# MicrocontrollerControl.net
KiCad netlist of a schematic drawn in Altium Designer
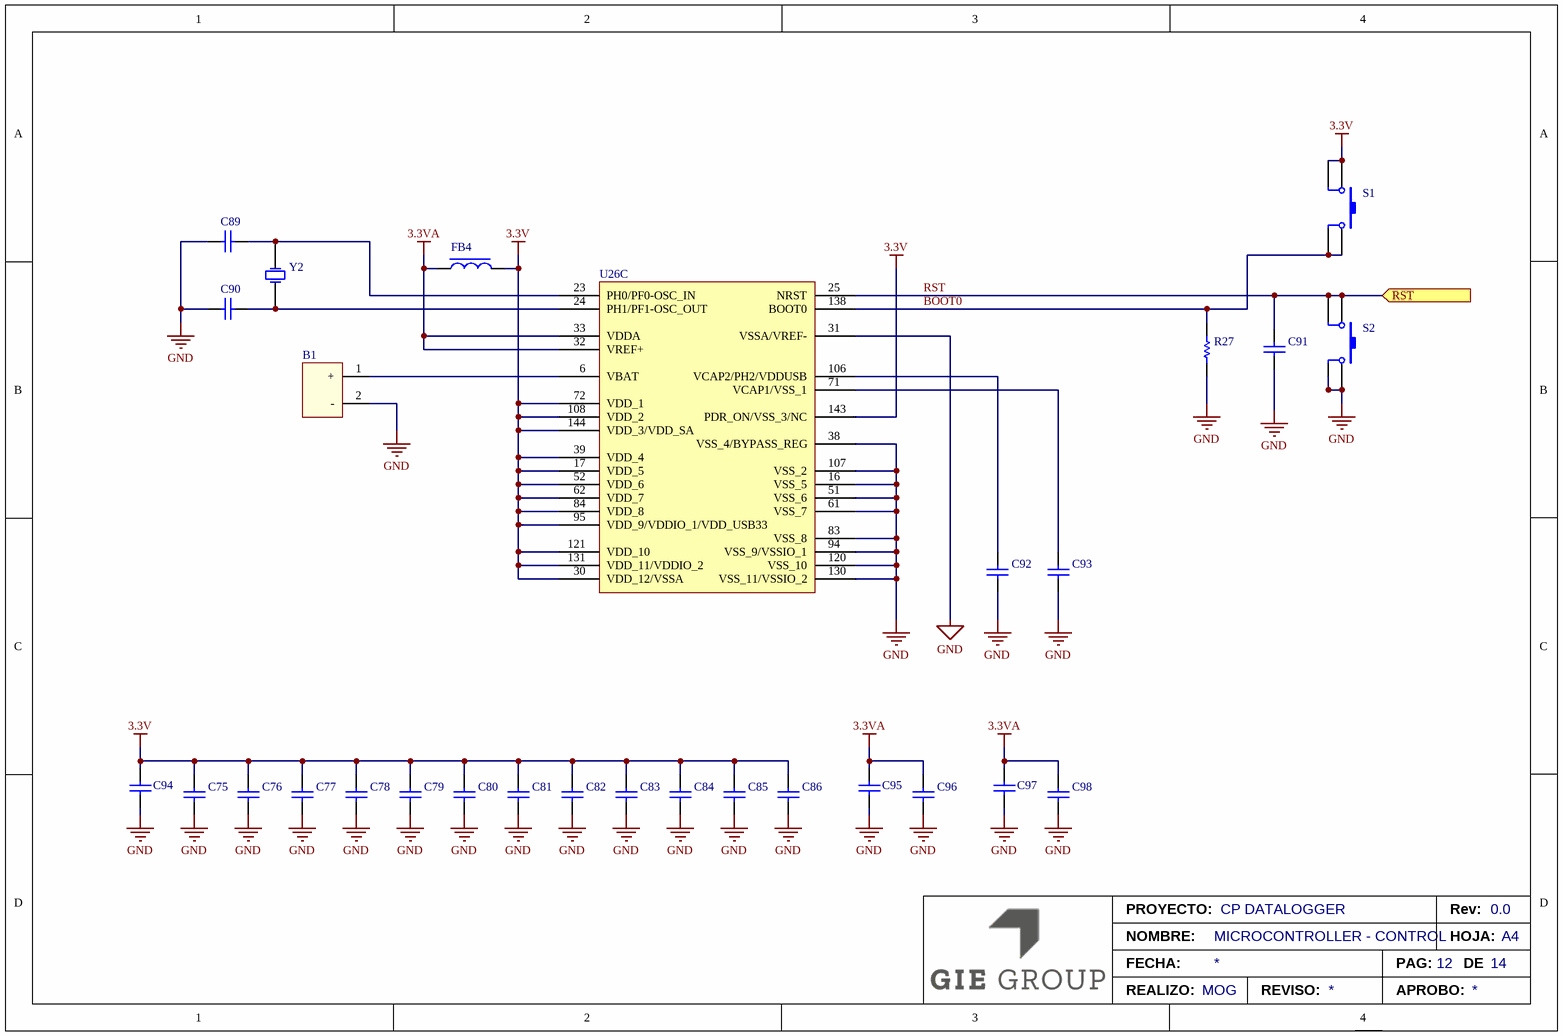
[diagram p0: MicrocontrollerControl.SchDoc]

(export (version "E")
  (design (tool "Eeschema 10.0.6"))
  (components
    (comp (ref "B1")
      (value "101")
      (footprint "Holder-CR2032-103")
      (description "HOLDER BATTERY COIN 20MM TH")
      (libsource (lib "Keystone") (part "Holder 101"))
    )
    (comp (ref "C75")
      (value "C0603C104K5RACAUTO")
      (footprint "CAP-0603")
      (description "CAP CER 0.1uF 50V X7R 0603")
      (fields (field (name "MANUFACTURER") "Kemet") (field (name "TOLERANCE") "10%"))
      (libsource (lib "Kemet") (part "C0603C104K5RACAUTO"))
    )
    (comp (ref "C76")
      (value "C0603C104K5RACAUTO")
      (footprint "CAP-0603")
      (description "CAP CER 0.1uF 50V X7R 0603")
      (fields (field (name "MANUFACTURER") "Kemet") (field (name "TOLERANCE") "10%"))
      (libsource (lib "Kemet") (part "C0603C104K5RACAUTO"))
    )
    (comp (ref "C77")
      (value "C0603C104K5RACAUTO")
      (footprint "CAP-0603")
      (description "CAP CER 0.1uF 50V X7R 0603")
      (fields (field (name "MANUFACTURER") "Kemet") (field (name "TOLERANCE") "10%"))
      (libsource (lib "Kemet") (part "C0603C104K5RACAUTO"))
    )
    (comp (ref "C78")
      (value "C0603C104K5RACAUTO")
      (footprint "CAP-0603")
      (description "CAP CER 0.1uF 50V X7R 0603")
      (fields (field (name "MANUFACTURER") "Kemet") (field (name "TOLERANCE") "10%"))
      (libsource (lib "Kemet") (part "C0603C104K5RACAUTO"))
    )
    (comp (ref "C79")
      (value "C0603C104K5RACAUTO")
      (footprint "CAP-0603")
      (description "CAP CER 0.1uF 50V X7R 0603")
      (fields (field (name "MANUFACTURER") "Kemet") (field (name "TOLERANCE") "10%"))
      (libsource (lib "Kemet") (part "C0603C104K5RACAUTO"))
    )
    (comp (ref "C80")
      (value "C0603C104K5RACAUTO")
      (footprint "CAP-0603")
      (description "CAP CER 0.1uF 50V X7R 0603")
      (fields (field (name "MANUFACTURER") "Kemet") (field (name "TOLERANCE") "10%"))
      (libsource (lib "Kemet") (part "C0603C104K5RACAUTO"))
    )
    (comp (ref "C81")
      (value "C0603C104K5RACAUTO")
      (footprint "CAP-0603")
      (description "CAP CER 0.1uF 50V X7R 0603")
      (fields (field (name "MANUFACTURER") "Kemet") (field (name "TOLERANCE") "10%"))
      (libsource (lib "Kemet") (part "C0603C104K5RACAUTO"))
    )
    (comp (ref "C82")
      (value "C0603C104K5RACAUTO")
      (footprint "CAP-0603")
      (description "CAP CER 0.1uF 50V X7R 0603")
      (fields (field (name "MANUFACTURER") "Kemet") (field (name "TOLERANCE") "10%"))
      (libsource (lib "Kemet") (part "C0603C104K5RACAUTO"))
    )
    (comp (ref "C83")
      (value "C0603C104K5RACAUTO")
      (footprint "CAP-0603")
      (description "CAP CER 0.1uF 50V X7R 0603")
      (fields (field (name "MANUFACTURER") "Kemet") (field (name "TOLERANCE") "10%"))
      (libsource (lib "Kemet") (part "C0603C104K5RACAUTO"))
    )
    (comp (ref "C84")
      (value "C0603C104K5RACAUTO")
      (footprint "CAP-0603")
      (description "CAP CER 0.1uF 50V X7R 0603")
      (fields (field (name "MANUFACTURER") "Kemet") (field (name "TOLERANCE") "10%"))
      (libsource (lib "Kemet") (part "C0603C104K5RACAUTO"))
    )
    (comp (ref "C85")
      (value "C0603C104K5RACAUTO")
      (footprint "CAP-0603")
      (description "CAP CER 0.1uF 50V X7R 0603")
      (fields (field (name "MANUFACTURER") "Kemet") (field (name "TOLERANCE") "10%"))
      (libsource (lib "Kemet") (part "C0603C104K5RACAUTO"))
    )
    (comp (ref "C86")
      (value "C0603C104K5RACAUTO")
      (footprint "CAP-0603")
      (description "CAP CER 0.1uF 50V X7R 0603")
      (fields (field (name "MANUFACTURER") "Kemet") (field (name "TOLERANCE") "10%"))
      (libsource (lib "Kemet") (part "C0603C104K5RACAUTO"))
    )
    (comp (ref "C89")
      (value "C0603C100K3GAC7867")
      (footprint "CAP-0603")
      (description "CAP CER 10 pF 25V C0G 0603")
      (fields (field (name "MANUFACTURER") "Kemet") (field (name "TOLERANCE") "10%"))
      (libsource (lib "Kemet") (part "C0603C100K3GAC7867"))
    )
    (comp (ref "C90")
      (value "C0603C100K3GAC7867")
      (footprint "CAP-0603")
      (description "CAP CER 10 pF 25V C0G 0603")
      (fields (field (name "MANUFACTURER") "Kemet") (field (name "TOLERANCE") "10%"))
      (libsource (lib "Kemet") (part "C0603C100K3GAC7867"))
    )
    (comp (ref "C91")
      (value "C0603C104K5RACAUTO")
      (footprint "CAP-0603")
      (description "CAP CER 0.1uF 50V X7R 0603")
      (fields (field (name "MANUFACTURER") "Kemet") (field (name "TOLERANCE") "10%"))
      (libsource (lib "Kemet") (part "C0603C104K5RACAUTO"))
    )
    (comp (ref "C92")
      (value "C0603C225M9PAC7867")
      (footprint "CAP-0603")
      (description "CAP CER 2.2uF 6.3V X5R 0603")
      (fields (field (name "MANUFACTURER") "Kemet") (field (name "TOLERANCE") "20%"))
      (libsource (lib "Kemet") (part "C0603C225M9PAC7867"))
    )
    (comp (ref "C93")
      (value "C0603C225M9PAC7867")
      (footprint "CAP-0603")
      (description "CAP CER 2.2uF 6.3V X5R 0603")
      (fields (field (name "MANUFACTURER") "Kemet") (field (name "TOLERANCE") "20%"))
      (libsource (lib "Kemet") (part "C0603C225M9PAC7867"))
    )
    (comp (ref "C94")
      (value "C0603C105M3RAC7867")
      (footprint "CAP-0603")
      (description "CAP CER 1uF 25V X7R 0603")
      (fields (field (name "MANUFACTURER") "Kemet") (field (name "TOLERANCE") "20%"))
      (libsource (lib "Kemet") (part "C0603C105M3RAC7867"))
    )
    (comp (ref "C95")
      (value "C0603C105M3RAC7867")
      (footprint "CAP-0603")
      (description "CAP CER 1uF 25V X7R 0603")
      (fields (field (name "MANUFACTURER") "Kemet") (field (name "TOLERANCE") "20%"))
      (libsource (lib "Kemet") (part "C0603C105M3RAC7867"))
    )
    (comp (ref "C96")
      (value "C0603C104K5RACAUTO")
      (footprint "CAP-0603")
      (description "CAP CER 0.1uF 50V X7R 0603")
      (fields (field (name "MANUFACTURER") "Kemet") (field (name "TOLERANCE") "10%"))
      (libsource (lib "Kemet") (part "C0603C104K5RACAUTO"))
    )
    (comp (ref "C97")
      (value "C0603C105M3RAC7867")
      (footprint "CAP-0603")
      (description "CAP CER 1uF 25V X7R 0603")
      (fields (field (name "MANUFACTURER") "Kemet") (field (name "TOLERANCE") "20%"))
      (libsource (lib "Kemet") (part "C0603C105M3RAC7867"))
    )
    (comp (ref "C98")
      (value "C0603C104K5RACAUTO")
      (footprint "CAP-0603")
      (description "CAP CER 0.1uF 50V X7R 0603")
      (fields (field (name "MANUFACTURER") "Kemet") (field (name "TOLERANCE") "10%"))
      (libsource (lib "Kemet") (part "C0603C104K5RACAUTO"))
    )
    (comp (ref "FB4")
      (value "Z0603C121GPWZT")
      (footprint "IND-0603")
      (description "Ferrite Bead 120Ohms 900mA 25% DCR=130m")
      (fields (field (name "MANUFACTURER") "Kemet"))
      (libsource (lib "Kemet") (part "Z0603C121GPWZT"))
    )
    (comp (ref "R27")
      (value "RC0603FR-0710KL")
      (footprint "RES-0603")
      (description "RES SMD 10.0K OHM 1% 1/10W 0603")
      (fields (field (name "TOLERANCE") "1%") (field (name "MANUFACTURER") "Yageo"))
      (libsource (lib "Yageo") (part "RC0603FR-0710KL"))
    )
    (comp (ref "S1")
      (value "KSC223JLFG")
      (footprint "KSC_J")
      (description "SWITCH TACTILE SPST-NO 0.01A 32V")
      (fields (field (name "MANUFACTURER") "C&K"))
      (libsource (lib "CK") (part "KSC223JLFG"))
    )
    (comp (ref "S2")
      (value "KSC223JLFG")
      (footprint "KSC_J")
      (description "SWITCH TACTILE SPST-NO 0.01A 32V")
      (fields (field (name "MANUFACTURER") "C&K"))
      (libsource (lib "CK") (part "KSC223JLFG"))
    )
    (comp (ref "U26")
      (value "STM32F429ZIT6")
      (footprint "LQFP144")
      (description "IC MCU 32BIT 2MB FLASH 144LQFP")
      (fields (field (name "MANUFACTURER") "STMicroelectronics"))
      (libsource (lib "STMicroelectronics") (part "STM32F429ZIT6"))
    )
    (comp (ref "Y2")
      (value "ABM7-16.000MHZ-D-2-Y-T")
      (footprint "XTAL-ABM7")
      (description "CRYSTAL 8.0000 MHZ 18PF SMD")
      (fields (field (name "MANUFACTURER") "Abracon"))
      (libsource (lib "Abracon") (part "ABM7-8.000MHZ-D2Y-T"))
    )
  )
  (nets
    (net (code "1") (name "/BOOT0") (class "Default")
      (node (ref "R27") (pin "2") (pinfunction "2_2") (pintype "passive"))
      (node (ref "S1") (pin "2") (pinfunction "2_2") (pintype "passive"))
      (node (ref "S1") (pin "3") (pinfunction "3_3") (pintype "passive"))
      (node (ref "U26") (pin "138") (pinfunction "BOOT0_138") (pintype "passive"))
    )
    (net (code "2") (name "/RST") (class "Default")
      (node (ref "C91") (pin "2") (pinfunction "2_2") (pintype "passive"))
      (node (ref "S2") (pin "1") (pinfunction "1_1") (pintype "passive"))
      (node (ref "S2") (pin "4") (pinfunction "4_4") (pintype "passive"))
      (node (ref "U26") (pin "25") (pinfunction "NRST_25") (pintype "passive"))
    )
    (net (code "3") (name "3.3V") (class "Default")
      (node (ref "C75") (pin "2") (pinfunction "2_2") (pintype "passive"))
      (node (ref "C76") (pin "2") (pinfunction "2_2") (pintype "passive"))
      (node (ref "C77") (pin "2") (pinfunction "2_2") (pintype "passive"))
      (node (ref "C78") (pin "2") (pinfunction "2_2") (pintype "passive"))
      (node (ref "C79") (pin "2") (pinfunction "2_2") (pintype "passive"))
      (node (ref "C80") (pin "2") (pinfunction "2_2") (pintype "passive"))
      (node (ref "C81") (pin "2") (pinfunction "2_2") (pintype "passive"))
      (node (ref "C82") (pin "2") (pinfunction "2_2") (pintype "passive"))
      (node (ref "C83") (pin "2") (pinfunction "2_2") (pintype "passive"))
      (node (ref "C84") (pin "2") (pinfunction "2_2") (pintype "passive"))
      (node (ref "C85") (pin "2") (pinfunction "2_2") (pintype "passive"))
      (node (ref "C86") (pin "2") (pinfunction "2_2") (pintype "passive"))
      (node (ref "C94") (pin "2") (pinfunction "2_2") (pintype "passive"))
      (node (ref "FB4") (pin "2") (pinfunction "2_2") (pintype "passive"))
      (node (ref "S1") (pin "1") (pinfunction "1_1") (pintype "passive"))
      (node (ref "S1") (pin "4") (pinfunction "4_4") (pintype "passive"))
      (node (ref "U26") (pin "108") (pinfunction "VDD_2_108") (pintype "passive"))
      (node (ref "U26") (pin "121") (pinfunction "VDD_10_121") (pintype "passive"))
      (node (ref "U26") (pin "131") (pinfunction "VDD_11/VDDIO_2_131") (pintype "passive"))
      (node (ref "U26") (pin "143") (pinfunction "PDR_ON/VSS_3/NC_143") (pintype "passive"))
      (node (ref "U26") (pin "144") (pinfunction "VDD_3/VDD_SA_144") (pintype "passive"))
      (node (ref "U26") (pin "17") (pinfunction "VDD_5_17") (pintype "passive"))
      (node (ref "U26") (pin "30") (pinfunction "VDD_12/VSSA_30") (pintype "passive"))
      (node (ref "U26") (pin "39") (pinfunction "VDD_4_39") (pintype "passive"))
      (node (ref "U26") (pin "52") (pinfunction "VDD_6_52") (pintype "passive"))
      (node (ref "U26") (pin "62") (pinfunction "VDD_7_62") (pintype "passive"))
      (node (ref "U26") (pin "72") (pinfunction "VDD_1_72") (pintype "passive"))
      (node (ref "U26") (pin "84") (pinfunction "VDD_8_84") (pintype "passive"))
      (node (ref "U26") (pin "95") (pinfunction "VDD_9/VDDIO_1/VDD_USB33_95") (pintype "passive"))
    )
    (net (code "4") (name "3.3VA") (class "Default")
      (node (ref "C95") (pin "2") (pinfunction "2_2") (pintype "passive"))
      (node (ref "C96") (pin "2") (pinfunction "2_2") (pintype "passive"))
      (node (ref "C97") (pin "2") (pinfunction "2_2") (pintype "passive"))
      (node (ref "C98") (pin "2") (pinfunction "2_2") (pintype "passive"))
      (node (ref "FB4") (pin "1") (pinfunction "1_1") (pintype "passive"))
      (node (ref "U26") (pin "32") (pinfunction "VREF+_32") (pintype "passive"))
      (node (ref "U26") (pin "33") (pinfunction "VDDA_33") (pintype "passive"))
    )
    (net (code "5") (name "GND") (class "Default")
      (node (ref "B1") (pin "2") (pinfunction "-_2") (pintype "passive"))
      (node (ref "C75") (pin "1") (pinfunction "1_1") (pintype "passive"))
      (node (ref "C76") (pin "1") (pinfunction "1_1") (pintype "passive"))
      (node (ref "C77") (pin "1") (pinfunction "1_1") (pintype "passive"))
      (node (ref "C78") (pin "1") (pinfunction "1_1") (pintype "passive"))
      (node (ref "C79") (pin "1") (pinfunction "1_1") (pintype "passive"))
      (node (ref "C80") (pin "1") (pinfunction "1_1") (pintype "passive"))
      (node (ref "C81") (pin "1") (pinfunction "1_1") (pintype "passive"))
      (node (ref "C82") (pin "1") (pinfunction "1_1") (pintype "passive"))
      (node (ref "C83") (pin "1") (pinfunction "1_1") (pintype "passive"))
      (node (ref "C84") (pin "1") (pinfunction "1_1") (pintype "passive"))
      (node (ref "C85") (pin "1") (pinfunction "1_1") (pintype "passive"))
      (node (ref "C86") (pin "1") (pinfunction "1_1") (pintype "passive"))
      (node (ref "C89") (pin "1") (pinfunction "1_1") (pintype "passive"))
      (node (ref "C90") (pin "1") (pinfunction "1_1") (pintype "passive"))
      (node (ref "C91") (pin "1") (pinfunction "1_1") (pintype "passive"))
      (node (ref "C92") (pin "1") (pinfunction "1_1") (pintype "passive"))
      (node (ref "C93") (pin "1") (pinfunction "1_1") (pintype "passive"))
      (node (ref "C94") (pin "1") (pinfunction "1_1") (pintype "passive"))
      (node (ref "C95") (pin "1") (pinfunction "1_1") (pintype "passive"))
      (node (ref "C96") (pin "1") (pinfunction "1_1") (pintype "passive"))
      (node (ref "C97") (pin "1") (pinfunction "1_1") (pintype "passive"))
      (node (ref "C98") (pin "1") (pinfunction "1_1") (pintype "passive"))
      (node (ref "R27") (pin "1") (pinfunction "1_1") (pintype "passive"))
      (node (ref "S2") (pin "2") (pinfunction "2_2") (pintype "passive"))
      (node (ref "S2") (pin "3") (pinfunction "3_3") (pintype "passive"))
      (node (ref "U26") (pin "107") (pinfunction "VSS_2_107") (pintype "passive"))
      (node (ref "U26") (pin "120") (pinfunction "VSS_10_120") (pintype "passive"))
      (node (ref "U26") (pin "130") (pinfunction "VSS_11/VSSIO_2_130") (pintype "passive"))
      (node (ref "U26") (pin "16") (pinfunction "VSS_5_16") (pintype "passive"))
      (node (ref "U26") (pin "31") (pinfunction "VSSA/VREF-_31") (pintype "passive"))
      (node (ref "U26") (pin "38") (pinfunction "VSS_4/BYPASS_REG_38") (pintype "passive"))
      (node (ref "U26") (pin "51") (pinfunction "VSS_6_51") (pintype "passive"))
      (node (ref "U26") (pin "61") (pinfunction "VSS_7_61") (pintype "passive"))
      (node (ref "U26") (pin "83") (pinfunction "VSS_8_83") (pintype "passive"))
      (node (ref "U26") (pin "94") (pinfunction "VSS_9/VSSIO_1_94") (pintype "passive"))
    )
    (net (code "6") (name "Net-(B1-+)") (class "Default")
      (node (ref "B1") (pin "1") (pinfunction "+_1") (pintype "passive"))
      (node (ref "U26") (pin "6") (pinfunction "VBAT_6") (pintype "passive"))
    )
    (net (code "7") (name "Net-(U26C-PH0{slash}PF0-OSC_IN)") (class "Default")
      (node (ref "C89") (pin "2") (pinfunction "2_2") (pintype "passive"))
      (node (ref "U26") (pin "23") (pinfunction "PH0/PF0-OSC_IN_23") (pintype "passive"))
      (node (ref "Y2") (pin "2") (pinfunction "OSC2_2") (pintype "passive"))
    )
    (net (code "8") (name "Net-(U26C-PH1{slash}PF1-OSC_OUT)") (class "Default")
      (node (ref "C90") (pin "2") (pinfunction "2_2") (pintype "passive"))
      (node (ref "U26") (pin "24") (pinfunction "PH1/PF1-OSC_OUT_24") (pintype "passive"))
      (node (ref "Y2") (pin "1") (pinfunction "OSC1_1") (pintype "passive"))
    )
    (net (code "9") (name "Net-(U26C-VCAP1{slash}VSS_1)") (class "Default")
      (node (ref "C93") (pin "2") (pinfunction "2_2") (pintype "passive"))
      (node (ref "U26") (pin "71") (pinfunction "VCAP1/VSS_1_71") (pintype "passive"))
    )
    (net (code "10") (name "Net-(U26C-VCAP2{slash}PH2{slash}VDDUSB)") (class "Default")
      (node (ref "C92") (pin "2") (pinfunction "2_2") (pintype "passive"))
      (node (ref "U26") (pin "106") (pinfunction "VCAP2/PH2/VDDUSB_106") (pintype "passive"))
    )
  )
)
